# IRKitESP8266.net
KiCad netlist of a schematic drawn in EAGLE
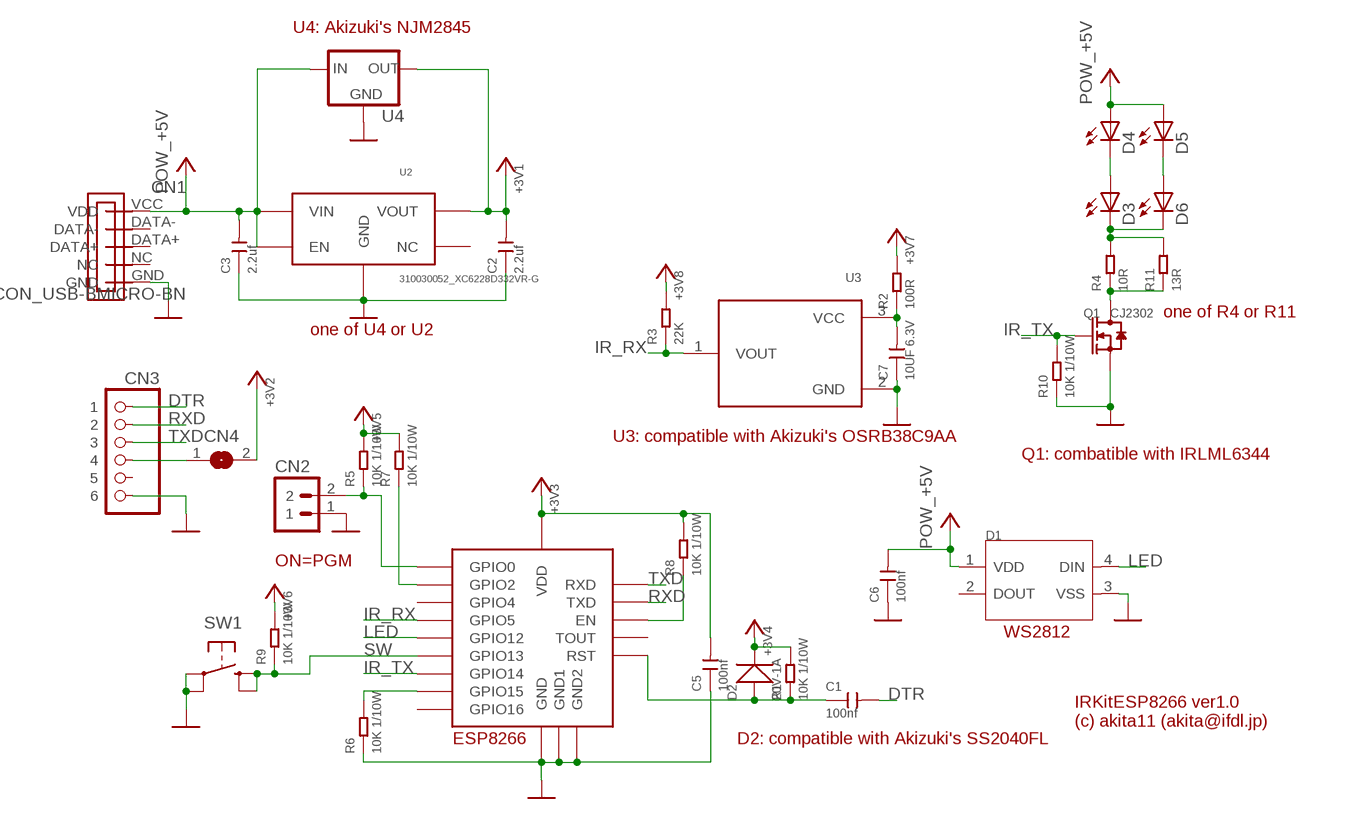
[diagram p0: schematic, sheet 1]

(export (version "E")
  (design (tool "Eeschema 10.0.6"))
  (components
    (comp (ref "C1")
      (value "100nf")
      (footprint "eagle-import:C0603")
      (fields (field (name "MPN") "CC0603KRX7R9BB104"))
      (libsource (lib "eagle-import") (part "CERAMIC-100NF-50V-10%-X7R(0603)"))
    )
    (comp (ref "C2")
      (value "2.2uf")
      (footprint "eagle-import:C0603")
      (fields (field (name "MPN") "CC0603KRX7R6BB225"))
      (libsource (lib "eagle-import") (part "CERAMIC-2.2UF-10V-10%-X7R(0603)"))
    )
    (comp (ref "C3")
      (value "2.2uf")
      (footprint "eagle-import:C0603")
      (fields (field (name "MPN") "CC0603KRX7R6BB225"))
      (libsource (lib "eagle-import") (part "CERAMIC-2.2UF-10V-10%-X7R(0603)"))
    )
    (comp (ref "C5")
      (value "100nf")
      (footprint "eagle-import:C0603")
      (fields (field (name "MPN") "CC0603KRX7R9BB104"))
      (libsource (lib "eagle-import") (part "CERAMIC-100NF-50V-10%-X7R(0603)"))
    )
    (comp (ref "C6")
      (value "100nf")
      (footprint "eagle-import:C0603")
      (fields (field (name "MPN") "CC0603KRX7R9BB104"))
      (libsource (lib "eagle-import") (part "CERAMIC-100NF-50V-10%-X7R(0603)"))
    )
    (comp (ref "C7")
      (value "10UF 6.3V")
      (footprint "eagle-import:C0603")
      (fields (field (name "MPN") "CC0603MRX5R5BB106"))
      (libsource (lib "eagle-import") (part "CERAMIC-10UF-6.3V-20%-X5R(0603)"))
    )
    (comp (ref "CN1")
      (value "CON_USB-BMICRO-BN")
      (footprint "eagle-import:MICRO-USB_B_NARROW")
      (libsource (lib "eagle-import") (part "CON_USB-BMICRO-BN"))
    )
    (comp (ref "CN2")
      (value "CON_PINHD-1X2PTH")
      (footprint "eagle-import:SPARKFUN_1X02")
      (libsource (lib "eagle-import") (part "CON_PINHD-1X2PTH"))
    )
    (comp (ref "CN3")
      (value "CON_PINHD-1X6")
      (footprint "eagle-import:1X06")
      (libsource (lib "eagle-import") (part "CON_PINHD-1X6"))
    )
    (comp (ref "CN4")
      (value "JUMPER_SJ")
      (footprint "eagle-import:JUMPER_SJ")
      (libsource (lib "eagle-import") (part "JUMPER_SJ"))
    )
    (comp (ref "D1")
      (value "SMD-RGB-LED-4P'WS2812B'")
      (footprint "eagle-import:LED4-SMD-5050")
      (libsource (lib "eagle-import") (part "SMD-RGB-LED-4P'WS2812B'"))
    )
    (comp (ref "D2")
      (value "20V-1A")
      (footprint "eagle-import:SOD-123")
      (fields (field (name "MPN") "B5819W"))
      (libsource (lib "eagle-import") (part "SMD-DIODE-SCHOTTKY-20V-1A(SOD-123)"))
    )
    (comp (ref "D3")
      (value "LED5MM")
      (footprint "eagle-import:SPARKFUN_LED5MM")
      (libsource (lib "eagle-import") (part "LED5MM"))
    )
    (comp (ref "D4")
      (value "LED5MM")
      (footprint "eagle-import:SPARKFUN_LED5MM")
      (libsource (lib "eagle-import") (part "LED5MM"))
    )
    (comp (ref "D5")
      (value "LED5MM")
      (footprint "eagle-import:SPARKFUN_LED5MM")
      (libsource (lib "eagle-import") (part "LED5MM"))
    )
    (comp (ref "D6")
      (value "LED5MM")
      (footprint "eagle-import:SPARKFUN_LED5MM")
      (libsource (lib "eagle-import") (part "LED5MM"))
    )
    (comp (ref "Q1")
      (value "CJ2302")
      (footprint "eagle-import:SOT-23")
      (libsource (lib "eagle-import") (part "SMD-MOSFET-N-CH-20V-2.1A-CJ2302(SOT-23)"))
    )
    (comp (ref "R1")
      (value "10K 1/10W")
      (footprint "eagle-import:R0603")
      (fields (field (name "MPN") "RC0603JR-0710KL"))
      (libsource (lib "eagle-import") (part "SMD-RES-10K-5%-1/10W(0603)"))
    )
    (comp (ref "R2")
      (value "100R")
      (footprint "eagle-import:R0603")
      (fields (field (name "MPN") "RC0603JR-07100RL"))
      (libsource (lib "eagle-import") (part "SMD-RES-100R-5%-1/10W(0603)"))
    )
    (comp (ref "R3")
      (value "22K")
      (footprint "eagle-import:R0603")
      (fields (field (name "MPN") "RC0603JR-0722KL"))
      (libsource (lib "eagle-import") (part "SMD-RES-22K-5%-1/10W(0603)"))
    )
    (comp (ref "R4")
      (value "10R")
      (footprint "eagle-import:R0603")
      (fields (field (name "MPN") "RC0603FR-0710RL"))
      (libsource (lib "eagle-import") (part "SMD-RES-10R-1%-1/10W(0603)"))
    )
    (comp (ref "R5")
      (value "10K 1/10W")
      (footprint "eagle-import:R0603")
      (fields (field (name "MPN") "RC0603JR-0710KL"))
      (libsource (lib "eagle-import") (part "SMD-RES-10K-5%-1/10W(0603)"))
    )
    (comp (ref "R6")
      (value "10K 1/10W")
      (footprint "eagle-import:R0603")
      (fields (field (name "MPN") "RC0603JR-0710KL"))
      (libsource (lib "eagle-import") (part "SMD-RES-10K-5%-1/10W(0603)"))
    )
    (comp (ref "R7")
      (value "10K 1/10W")
      (footprint "eagle-import:R0603")
      (fields (field (name "MPN") "RC0603JR-0710KL"))
      (libsource (lib "eagle-import") (part "SMD-RES-10K-5%-1/10W(0603)"))
    )
    (comp (ref "R8")
      (value "10K 1/10W")
      (footprint "eagle-import:R0603")
      (fields (field (name "MPN") "RC0603JR-0710KL"))
      (libsource (lib "eagle-import") (part "SMD-RES-10K-5%-1/10W(0603)"))
    )
    (comp (ref "R9")
      (value "10K 1/10W")
      (footprint "eagle-import:R0603")
      (fields (field (name "MPN") "RC0603JR-0710KL"))
      (libsource (lib "eagle-import") (part "SMD-RES-10K-5%-1/10W(0603)"))
    )
    (comp (ref "R10")
      (value "10K 1/10W")
      (footprint "eagle-import:R0603")
      (fields (field (name "MPN") "RC0603JR-0710KL"))
      (libsource (lib "eagle-import") (part "SMD-RES-10K-5%-1/10W(0603)"))
    )
    (comp (ref "R11")
      (value "13R")
      (footprint "eagle-import:R1206")
      (fields (field (name "MPN") "RC1206JR-0713RL"))
      (libsource (lib "eagle-import") (part "SMD-RES-13R-5%-1/4W(1206)"))
    )
    (comp (ref "SW1")
      (value "SW_TACTTH")
      (footprint "eagle-import:SW_B3F-10XX")
      (fields (field (name "MPN") "B3F-1000"))
      (libsource (lib "eagle-import") (part "SW_TACTTH"))
    )
    (comp (ref "U1")
      (value "MOD_ESP8266WROOM02")
      (footprint "eagle-import:MOD_ESP8266WROOM02")
      (libsource (lib "eagle-import") (part "MOD_ESP8266WROOM02"))
    )
    (comp (ref "U2")
      (value "310030052_XC6228D332VR-G")
      (footprint "eagle-import:SOT25J")
      (libsource (lib "eagle-import") (part "310030052_XC6228D332VR-G"))
    )
    (comp (ref "U3")
      (value "TSOP382")
      (footprint "eagle-import:TSOP382")
      (libsource (lib "eagle-import") (part "TSOP382"))
    )
    (comp (ref "U4")
      (value "REG_78XXTO252-3")
      (footprint "eagle-import:TO-252-3")
      (libsource (lib "eagle-import") (part "REG_78XXTO252-3"))
    )
  )
  (nets
    (net (code "1") (name "/DTR") (class "Default")
      (node (ref "C1") (pin "2") (pinfunction "2_2") (pintype "passive"))
      (node (ref "CN3") (pin "1") (pinfunction "1_1") (pintype "passive"))
    )
    (net (code "2") (name "/IR_RX") (class "Default")
      (node (ref "R3") (pin "1") (pinfunction "1_1") (pintype "passive"))
      (node (ref "U1") (pin "P$14") (pinfunction "GPIO5_P$14") (pintype "bidirectional"))
      (node (ref "U3") (pin "1") (pinfunction "VOUT_1") (pintype "bidirectional"))
    )
    (net (code "3") (name "/IR_TX") (class "Default")
      (node (ref "Q1") (pin "1") (pinfunction "G_1") (pintype "passive"))
      (node (ref "R10") (pin "2") (pinfunction "2_2") (pintype "passive"))
      (node (ref "U1") (pin "P$3") (pinfunction "GPIO14_P$3") (pintype "bidirectional"))
    )
    (net (code "4") (name "/LED") (class "Default")
      (node (ref "D1") (pin "4") (pinfunction "DIN_4") (pintype "bidirectional"))
      (node (ref "U1") (pin "P$4") (pinfunction "GPIO12_P$4") (pintype "bidirectional"))
    )
    (net (code "5") (name "/RXD") (class "Default")
      (node (ref "CN3") (pin "2") (pinfunction "2_2") (pintype "passive"))
      (node (ref "U1") (pin "P$12") (pinfunction "TXD_P$12") (pintype "bidirectional"))
    )
    (net (code "6") (name "/SW") (class "Default")
      (node (ref "R9") (pin "1") (pinfunction "1_1") (pintype "passive"))
      (node (ref "SW1") (pin "1") (pinfunction "S_1") (pintype "passive"))
      (node (ref "SW1") (pin "2") (pinfunction "S1_2") (pintype "passive"))
      (node (ref "U1") (pin "P$5") (pinfunction "GPIO13_P$5") (pintype "bidirectional"))
    )
    (net (code "7") (name "/TXD") (class "Default")
      (node (ref "CN3") (pin "3") (pinfunction "3_3") (pintype "passive"))
      (node (ref "U1") (pin "P$11") (pinfunction "RXD_P$11") (pintype "bidirectional"))
    )
    (net (code "8") (name "Net-(CN3-Pad4)") (class "Default")
      (node (ref "CN3") (pin "4") (pinfunction "4_4") (pintype "passive"))
      (node (ref "CN4") (pin "1") (pinfunction "1_1") (pintype "passive"))
    )
    (net (code "9") (name "Net-(D3-C)") (class "Default")
      (node (ref "D3") (pin "K") (pinfunction "C_K") (pintype "passive"))
      (node (ref "D6") (pin "K") (pinfunction "C_K") (pintype "passive"))
      (node (ref "R11") (pin "2") (pinfunction "2_2") (pintype "passive"))
      (node (ref "R4") (pin "2") (pinfunction "2_2") (pintype "passive"))
    )
    (net (code "10") (name "Net-(D4-C)") (class "Default")
      (node (ref "D3") (pin "A") (pinfunction "A_A") (pintype "passive"))
      (node (ref "D4") (pin "K") (pinfunction "C_K") (pintype "passive"))
    )
    (net (code "11") (name "Net-(D5-C)") (class "Default")
      (node (ref "D5") (pin "K") (pinfunction "C_K") (pintype "passive"))
      (node (ref "D6") (pin "A") (pinfunction "A_A") (pintype "passive"))
    )
    (net (code "12") (name "Net-(Q1-D)") (class "Default")
      (node (ref "Q1") (pin "3") (pinfunction "D_3") (pintype "passive"))
      (node (ref "R11") (pin "1") (pinfunction "1_1") (pintype "passive"))
      (node (ref "R4") (pin "1") (pinfunction "1_1") (pintype "passive"))
    )
    (net (code "13") (name "Net-(U1-EN)") (class "Default")
      (node (ref "R8") (pin "1") (pinfunction "1_1") (pintype "passive"))
      (node (ref "U1") (pin "P$2") (pinfunction "EN_P$2") (pintype "bidirectional"))
    )
    (net (code "14") (name "Net-(U1-GPIO0)") (class "Default")
      (node (ref "CN2") (pin "2") (pinfunction "2_2") (pintype "passive"))
      (node (ref "R5") (pin "1") (pinfunction "1_1") (pintype "passive"))
      (node (ref "U1") (pin "P$8") (pinfunction "GPIO0_P$8") (pintype "bidirectional"))
    )
    (net (code "15") (name "Net-(U1-GPIO2)") (class "Default")
      (node (ref "R7") (pin "1") (pinfunction "1_1") (pintype "passive"))
      (node (ref "U1") (pin "P$7") (pinfunction "GPIO2_P$7") (pintype "bidirectional"))
    )
    (net (code "16") (name "Net-(U1-GPIO15)") (class "Default")
      (node (ref "R6") (pin "2") (pinfunction "2_2") (pintype "passive"))
      (node (ref "U1") (pin "P$6") (pinfunction "GPIO15_P$6") (pintype "bidirectional"))
    )
    (net (code "17") (name "Net-(U1-RST)") (class "Default")
      (node (ref "C1") (pin "1") (pinfunction "1_1") (pintype "passive"))
      (node (ref "D2") (pin "+") (pinfunction "+_+") (pintype "passive"))
      (node (ref "R1") (pin "1") (pinfunction "1_1") (pintype "passive"))
      (node (ref "U1") (pin "P$15") (pinfunction "RST_P$15") (pintype "bidirectional"))
    )
    (net (code "18") (name "Net-(U3-VCC)") (class "Default")
      (node (ref "C7") (pin "2") (pinfunction "2_2") (pintype "passive"))
      (node (ref "R2") (pin "1") (pinfunction "1_1") (pintype "passive"))
      (node (ref "U3") (pin "3") (pinfunction "VCC_3") (pintype "bidirectional"))
    )
    (net (code "19") (name "POW_+3V3") (class "Default")
      (node (ref "C2") (pin "2") (pinfunction "2_2") (pintype "passive"))
      (node (ref "C5") (pin "2") (pinfunction "2_2") (pintype "passive"))
      (node (ref "CN4") (pin "2") (pinfunction "2_2") (pintype "passive"))
      (node (ref "D2") (pin "-") (pinfunction "-_-") (pintype "passive"))
      (node (ref "R1") (pin "2") (pinfunction "2_2") (pintype "passive"))
      (node (ref "R2") (pin "2") (pinfunction "2_2") (pintype "passive"))
      (node (ref "R3") (pin "2") (pinfunction "2_2") (pintype "passive"))
      (node (ref "R5") (pin "2") (pinfunction "2_2") (pintype "passive"))
      (node (ref "R7") (pin "2") (pinfunction "2_2") (pintype "passive"))
      (node (ref "R8") (pin "2") (pinfunction "2_2") (pintype "passive"))
      (node (ref "R9") (pin "2") (pinfunction "2_2") (pintype "passive"))
      (node (ref "U1") (pin "P$1") (pinfunction "VDD_P$1") (pintype "bidirectional"))
      (node (ref "U2") (pin "P$5") (pinfunction "VOUT_P$5") (pintype "bidirectional"))
      (node (ref "U4") (pin "P$3") (pinfunction "OUT_P$3") (pintype "output"))
    )
    (net (code "20") (name "POW_+5V") (class "Default")
      (node (ref "C3") (pin "2") (pinfunction "2_2") (pintype "passive"))
      (node (ref "C6") (pin "2") (pinfunction "2_2") (pintype "passive"))
      (node (ref "CN1") (pin "VCC") (pinfunction "VDD_VCC") (pintype "power_in"))
      (node (ref "D1") (pin "1") (pinfunction "VDD_1") (pintype "bidirectional"))
      (node (ref "D4") (pin "A") (pinfunction "A_A") (pintype "passive"))
      (node (ref "D5") (pin "A") (pinfunction "A_A") (pintype "passive"))
      (node (ref "U2") (pin "P$1") (pinfunction "VIN_P$1") (pintype "bidirectional"))
      (node (ref "U2") (pin "P$3") (pinfunction "EN_P$3") (pintype "bidirectional"))
      (node (ref "U4") (pin "P$1") (pinfunction "IN_P$1") (pintype "input"))
    )
    (net (code "21") (name "POW_GND") (class "Default")
      (node (ref "C2") (pin "1") (pinfunction "1_1") (pintype "passive"))
      (node (ref "C3") (pin "1") (pinfunction "1_1") (pintype "passive"))
      (node (ref "C5") (pin "1") (pinfunction "1_1") (pintype "passive"))
      (node (ref "C6") (pin "1") (pinfunction "1_1") (pintype "passive"))
      (node (ref "C7") (pin "1") (pinfunction "1_1") (pintype "passive"))
      (node (ref "CN1") (pin "GND") (pinfunction "GND_GND") (pintype "power_in"))
      (node (ref "CN2") (pin "1") (pinfunction "1_1") (pintype "passive"))
      (node (ref "CN3") (pin "6") (pinfunction "6_6") (pintype "passive"))
      (node (ref "D1") (pin "3") (pinfunction "VSS_3") (pintype "bidirectional"))
      (node (ref "Q1") (pin "2") (pinfunction "S_2") (pintype "passive"))
      (node (ref "R10") (pin "1") (pinfunction "1_1") (pintype "passive"))
      (node (ref "R6") (pin "1") (pinfunction "1_1") (pintype "passive"))
      (node (ref "SW1") (pin "3") (pinfunction "P_3") (pintype "passive"))
      (node (ref "SW1") (pin "4") (pinfunction "P1_4") (pintype "passive"))
      (node (ref "U1") (pin "P$13") (pinfunction "GND1_P$13") (pintype "bidirectional"))
      (node (ref "U1") (pin "P$18") (pinfunction "GND2_P$18") (pintype "bidirectional"))
      (node (ref "U1") (pin "P$9") (pinfunction "GND_P$9") (pintype "bidirectional"))
      (node (ref "U2") (pin "P$2") (pinfunction "GND_P$2") (pintype "bidirectional"))
      (node (ref "U3") (pin "2") (pinfunction "GND_2") (pintype "bidirectional"))
      (node (ref "U4") (pin "P$2") (pinfunction "GND_P$2") (pintype "input"))
    )
    (net (code "22") (name "unconnected-(CN1-PadDATA+)") (class "Default")
      (node (ref "CN1") (pin "DATA+") (pinfunction "DATA+_DATA+") (pintype "bidirectional"))
    )
    (net (code "23") (name "unconnected-(CN1-PadDATA-)") (class "Default")
      (node (ref "CN1") (pin "DATA-") (pinfunction "DATA-_DATA-") (pintype "bidirectional"))
    )
    (net (code "24") (name "unconnected-(CN1-PadNC)") (class "Default")
      (node (ref "CN1") (pin "NC") (pinfunction "NC_NC") (pintype "bidirectional"))
    )
    (net (code "25") (name "unconnected-(CN3-Pad5)") (class "Default")
      (node (ref "CN3") (pin "5") (pinfunction "5_5") (pintype "passive"))
    )
    (net (code "26") (name "unconnected-(D1-DOUT-Pad2)") (class "Default")
      (node (ref "D1") (pin "2") (pinfunction "DOUT_2") (pintype "bidirectional"))
    )
    (net (code "27") (name "unconnected-(U1-GPIO4-PadP$10)") (class "Default")
      (node (ref "U1") (pin "P$10") (pinfunction "GPIO4_P$10") (pintype "bidirectional"))
    )
    (net (code "28") (name "unconnected-(U1-GPIO16-PadP$17)") (class "Default")
      (node (ref "U1") (pin "P$17") (pinfunction "GPIO16_P$17") (pintype "bidirectional"))
    )
    (net (code "29") (name "unconnected-(U1-TOUT-PadP$16)") (class "Default")
      (node (ref "U1") (pin "P$16") (pinfunction "TOUT_P$16") (pintype "bidirectional"))
    )
    (net (code "30") (name "unconnected-(U2-NC-PadP$4)") (class "Default")
      (node (ref "U2") (pin "P$4") (pinfunction "NC_P$4") (pintype "bidirectional"))
    )
  )
)
